# DAC.net
KiCad netlist of a schematic drawn in Altium Designer
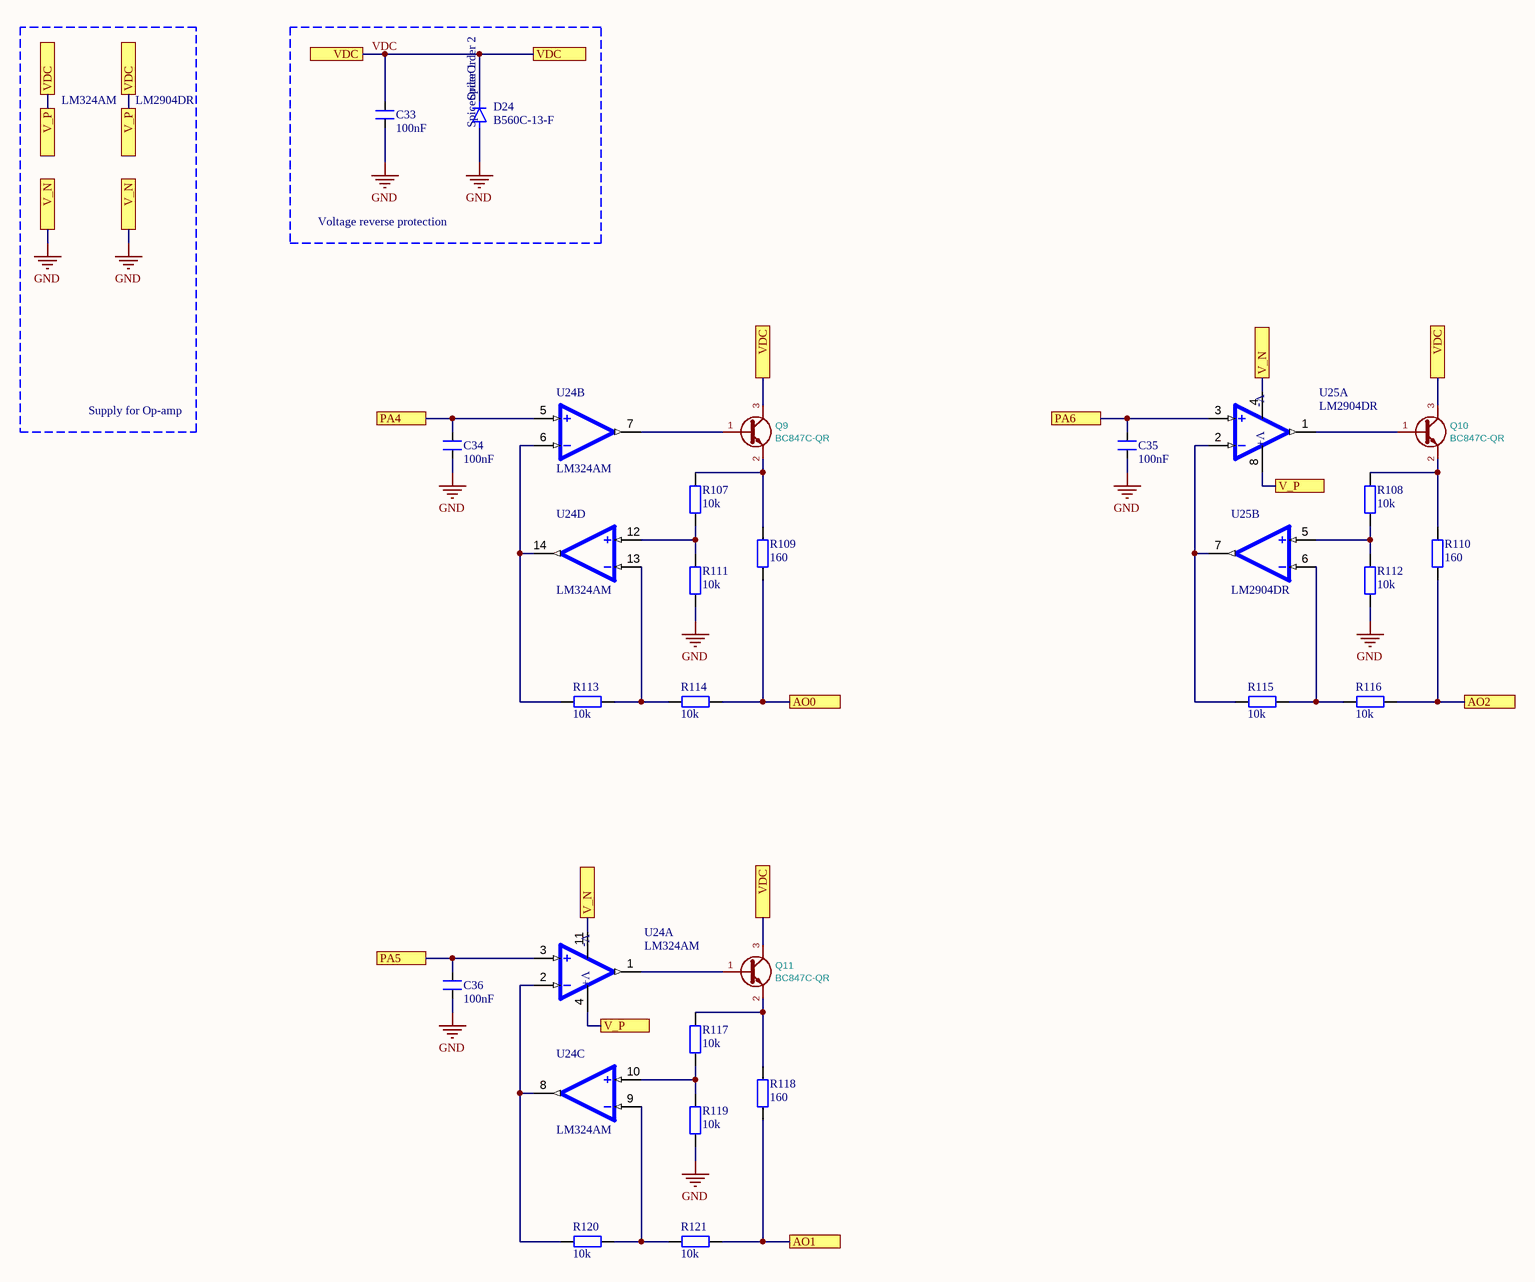
[diagram p0: DAC.SchDoc]

(export (version "E")
  (design (tool "Eeschema 10.0.6"))
  (components
    (comp (ref "C33")
      (value "100nF")
      (footprint "FP-C0603C-CF-IPC_A")
      (description "Capacitor (Semiconductor SIM Model)")
      (fields (field (name "PUBLISHER") "Altium Limited"))
      (libsource (lib "LIBRARY") (part "CN-SEMI-DIP"))
    )
    (comp (ref "C34")
      (value "100nF")
      (footprint "FP-C0603C-CF-IPC_A")
      (description "Capacitor (Semiconductor SIM Model)")
      (fields (field (name "PUBLISHER") "Altium Limited"))
      (libsource (lib "LIBRARY") (part "CN-SEMI-DIP"))
    )
    (comp (ref "C35")
      (value "100nF")
      (footprint "FP-C0603C-CF-IPC_A")
      (description "Capacitor (Semiconductor SIM Model)")
      (fields (field (name "PUBLISHER") "Altium Limited"))
      (libsource (lib "LIBRARY") (part "CN-SEMI-DIP"))
    )
    (comp (ref "C36")
      (value "100nF")
      (footprint "FP-C0603C-CF-IPC_A")
      (description "Capacitor (Semiconductor SIM Model)")
      (fields (field (name "PUBLISHER") "Altium Limited"))
      (libsource (lib "LIBRARY") (part "CN-SEMI-DIP"))
    )
    (comp (ref "D24")
      (value "B560C-13-F")
      (footprint "SMC")
      (description "Diode Schottky 60 V 5A Surface Mount SMC")
      (fields (field (name "MF") "Diodes Inc."))
      (libsource (lib "B560C-13-F") (part "B560C-13-F"))
    )
    (comp (ref "Q9")
      (value "BC847C-QR")
      (footprint "SOT95P240X111-3N")
      (libsource (lib "Transistor_BJT") (part "BC847"))
    )
    (comp (ref "Q10")
      (value "BC847C-QR")
      (footprint "SOT95P240X111-3N")
      (libsource (lib "Transistor_BJT") (part "BC847"))
    )
    (comp (ref "Q11")
      (value "BC847C-QR")
      (footprint "SOT95P240X111-3N")
      (libsource (lib "Transistor_BJT") (part "BC847"))
    )
    (comp (ref "R107")
      (value "10k")
      (footprint "tro smd 0603")
      (description "RES")
      (libsource (lib "AUSB") (part "Tro 0603 1% 10k"))
    )
    (comp (ref "R108")
      (value "10k")
      (footprint "tro smd 0603")
      (description "RES")
      (libsource (lib "AUSB") (part "Tro 0603 1% 10k"))
    )
    (comp (ref "R109")
      (value "160")
      (footprint "tro smd 0603")
      (description "RES")
      (libsource (lib "AUSB") (part "Tro 0603 1% 10k"))
    )
    (comp (ref "R110")
      (value "160")
      (footprint "tro smd 0603")
      (description "RES")
      (libsource (lib "AUSB") (part "Tro 0603 1% 10k"))
    )
    (comp (ref "R111")
      (value "10k")
      (footprint "tro smd 0603")
      (description "RES")
      (libsource (lib "AUSB") (part "Tro 0603 1% 10k"))
    )
    (comp (ref "R112")
      (value "10k")
      (footprint "tro smd 0603")
      (description "RES")
      (libsource (lib "AUSB") (part "Tro 0603 1% 10k"))
    )
    (comp (ref "R113")
      (value "10k")
      (footprint "tro smd 0603")
      (description "RES")
      (libsource (lib "AUSB") (part "Tro 0603 1% 10k"))
    )
    (comp (ref "R114")
      (value "10k")
      (footprint "tro smd 0603")
      (description "RES")
      (libsource (lib "AUSB") (part "Tro 0603 1% 10k"))
    )
    (comp (ref "R115")
      (value "10k")
      (footprint "tro smd 0603")
      (description "RES")
      (libsource (lib "AUSB") (part "Tro 0603 1% 10k"))
    )
    (comp (ref "R116")
      (value "10k")
      (footprint "tro smd 0603")
      (description "RES")
      (libsource (lib "AUSB") (part "Tro 0603 1% 10k"))
    )
    (comp (ref "R117")
      (value "10k")
      (footprint "tro smd 0603")
      (description "RES")
      (libsource (lib "AUSB") (part "Tro 0603 1% 10k"))
    )
    (comp (ref "R118")
      (value "160")
      (footprint "tro smd 0603")
      (description "RES")
      (libsource (lib "AUSB") (part "Tro 0603 1% 10k"))
    )
    (comp (ref "R119")
      (value "10k")
      (footprint "tro smd 0603")
      (description "RES")
      (libsource (lib "AUSB") (part "Tro 0603 1% 10k"))
    )
    (comp (ref "R120")
      (value "10k")
      (footprint "tro smd 0603")
      (description "RES")
      (libsource (lib "AUSB") (part "Tro 0603 1% 10k"))
    )
    (comp (ref "R121")
      (value "10k")
      (footprint "tro smd 0603")
      (description "RES")
      (libsource (lib "AUSB") (part "Tro 0603 1% 10k"))
    )
    (comp (ref "U24")
      (value "LM324AM")
      (footprint "SOIC127P600X175-14N")
      (description "Low power general-purpose quad operational amplifier 14-SOIC 0 to 70")
      (fields (field (name "MF") "Texas Instruments"))
      (libsource (lib "LM324AM_NOPB") (part "LM324AM/NOPB"))
    )
    (comp (ref "U25")
      (value "LM2904DR")
      (footprint "SOIC127P599X175-8N")
      (description "Dual, 26-V, 700-kHz operational amplifier")
      (fields (field (name "MF") "Texas Instruments"))
      (libsource (lib "LM2904DR") (part "LM2904DR"))
    )
  )
  (nets
    (net (code "1") (name "/AO0") (class "Default")
      (node (ref "R109") (pin "1") (pinfunction "1_1") (pintype "passive"))
      (node (ref "R114") (pin "1") (pinfunction "1_1") (pintype "passive"))
    )
    (net (code "2") (name "/AO1") (class "Default")
      (node (ref "R118") (pin "1") (pinfunction "1_1") (pintype "passive"))
      (node (ref "R121") (pin "1") (pinfunction "1_1") (pintype "passive"))
    )
    (net (code "3") (name "/AO2") (class "Default")
      (node (ref "R110") (pin "1") (pinfunction "1_1") (pintype "passive"))
      (node (ref "R116") (pin "1") (pinfunction "1_1") (pintype "passive"))
    )
    (net (code "4") (name "/PA4") (class "Default")
      (node (ref "C34") (pin "1") (pinfunction "1_1") (pintype "passive"))
      (node (ref "U24") (pin "5") (pinfunction "IN2+_5") (pintype "input"))
    )
    (net (code "5") (name "/PA5") (class "Default")
      (node (ref "C36") (pin "1") (pinfunction "1_1") (pintype "passive"))
      (node (ref "U24") (pin "3") (pinfunction "IN1+_3") (pintype "input"))
    )
    (net (code "6") (name "/PA6") (class "Default")
      (node (ref "C35") (pin "1") (pinfunction "1_1") (pintype "passive"))
      (node (ref "U25") (pin "3") (pinfunction "IN1+_3") (pintype "input"))
    )
    (net (code "7") (name "/VDC") (class "Default")
      (node (ref "C33") (pin "1") (pinfunction "1_1") (pintype "passive"))
      (node (ref "D24") (pin "C") (pinfunction "C_C") (pintype "passive"))
      (node (ref "Q10") (pin "3") (pinfunction "C_3") (pintype "passive"))
      (node (ref "Q11") (pin "3") (pinfunction "C_3") (pintype "passive"))
      (node (ref "Q9") (pin "3") (pinfunction "C_3") (pintype "passive"))
      (node (ref "U24") (pin "4") (pinfunction "V+_4") (pintype "power_in"))
      (node (ref "U25") (pin "8") (pinfunction "V+_8") (pintype "power_in"))
    )
    (net (code "8") (name "GND") (class "Default")
      (node (ref "C33") (pin "2") (pinfunction "2_2") (pintype "passive"))
      (node (ref "C34") (pin "2") (pinfunction "2_2") (pintype "passive"))
      (node (ref "C35") (pin "2") (pinfunction "2_2") (pintype "passive"))
      (node (ref "C36") (pin "2") (pinfunction "2_2") (pintype "passive"))
      (node (ref "D24") (pin "A") (pinfunction "A_A") (pintype "passive"))
      (node (ref "R111") (pin "1") (pinfunction "1_1") (pintype "passive"))
      (node (ref "R112") (pin "1") (pinfunction "1_1") (pintype "passive"))
      (node (ref "R119") (pin "1") (pinfunction "1_1") (pintype "passive"))
      (node (ref "U24") (pin "11") (pinfunction "GND_11") (pintype "power_in"))
      (node (ref "U25") (pin "4") (pinfunction "V-_4") (pintype "power_in"))
    )
    (net (code "9") (name "Net-(Q9-B)") (class "Default")
      (node (ref "Q9") (pin "1") (pinfunction "B_1") (pintype "passive"))
      (node (ref "U24") (pin "7") (pinfunction "OUT2_7") (pintype "output"))
    )
    (net (code "10") (name "Net-(Q9-E)") (class "Default")
      (node (ref "Q9") (pin "2") (pinfunction "E_2") (pintype "passive"))
      (node (ref "R107") (pin "2") (pinfunction "2_2") (pintype "passive"))
      (node (ref "R109") (pin "2") (pinfunction "2_2") (pintype "passive"))
    )
    (net (code "11") (name "Net-(Q10-B)") (class "Default")
      (node (ref "Q10") (pin "1") (pinfunction "B_1") (pintype "passive"))
      (node (ref "U25") (pin "1") (pinfunction "OUT1_1") (pintype "output"))
    )
    (net (code "12") (name "Net-(Q10-E)") (class "Default")
      (node (ref "Q10") (pin "2") (pinfunction "E_2") (pintype "passive"))
      (node (ref "R108") (pin "2") (pinfunction "2_2") (pintype "passive"))
      (node (ref "R110") (pin "2") (pinfunction "2_2") (pintype "passive"))
    )
    (net (code "13") (name "Net-(Q11-B)") (class "Default")
      (node (ref "Q11") (pin "1") (pinfunction "B_1") (pintype "passive"))
      (node (ref "U24") (pin "1") (pinfunction "OUT1_1") (pintype "output"))
    )
    (net (code "14") (name "Net-(Q11-E)") (class "Default")
      (node (ref "Q11") (pin "2") (pinfunction "E_2") (pintype "passive"))
      (node (ref "R117") (pin "2") (pinfunction "2_2") (pintype "passive"))
      (node (ref "R118") (pin "2") (pinfunction "2_2") (pintype "passive"))
    )
    (net (code "15") (name "Net-(U24A-IN1-)") (class "Default")
      (node (ref "R120") (pin "2") (pinfunction "2_2") (pintype "passive"))
      (node (ref "U24") (pin "2") (pinfunction "IN1-_2") (pintype "input"))
      (node (ref "U24") (pin "8") (pinfunction "OUT3_8") (pintype "output"))
    )
    (net (code "16") (name "Net-(U24B-IN2-)") (class "Default")
      (node (ref "R113") (pin "2") (pinfunction "2_2") (pintype "passive"))
      (node (ref "U24") (pin "14") (pinfunction "OUT4_14") (pintype "output"))
      (node (ref "U24") (pin "6") (pinfunction "IN2-_6") (pintype "input"))
    )
    (net (code "17") (name "Net-(U24C-IN3+)") (class "Default")
      (node (ref "R117") (pin "1") (pinfunction "1_1") (pintype "passive"))
      (node (ref "R119") (pin "2") (pinfunction "2_2") (pintype "passive"))
      (node (ref "U24") (pin "10") (pinfunction "IN3+_10") (pintype "input"))
    )
    (net (code "18") (name "Net-(U24C-IN3-)") (class "Default")
      (node (ref "R120") (pin "1") (pinfunction "1_1") (pintype "passive"))
      (node (ref "R121") (pin "2") (pinfunction "2_2") (pintype "passive"))
      (node (ref "U24") (pin "9") (pinfunction "IN3-_9") (pintype "input"))
    )
    (net (code "19") (name "Net-(U24D-IN4+)") (class "Default")
      (node (ref "R107") (pin "1") (pinfunction "1_1") (pintype "passive"))
      (node (ref "R111") (pin "2") (pinfunction "2_2") (pintype "passive"))
      (node (ref "U24") (pin "12") (pinfunction "IN4+_12") (pintype "input"))
    )
    (net (code "20") (name "Net-(U24D-IN4-)") (class "Default")
      (node (ref "R113") (pin "1") (pinfunction "1_1") (pintype "passive"))
      (node (ref "R114") (pin "2") (pinfunction "2_2") (pintype "passive"))
      (node (ref "U24") (pin "13") (pinfunction "IN4-_13") (pintype "input"))
    )
    (net (code "21") (name "Net-(U25A-IN1-)") (class "Default")
      (node (ref "R115") (pin "2") (pinfunction "2_2") (pintype "passive"))
      (node (ref "U25") (pin "2") (pinfunction "IN1-_2") (pintype "input"))
      (node (ref "U25") (pin "7") (pinfunction "OUT2_7") (pintype "output"))
    )
    (net (code "22") (name "Net-(U25B-IN2+)") (class "Default")
      (node (ref "R108") (pin "1") (pinfunction "1_1") (pintype "passive"))
      (node (ref "R112") (pin "2") (pinfunction "2_2") (pintype "passive"))
      (node (ref "U25") (pin "5") (pinfunction "IN2+_5") (pintype "input"))
    )
    (net (code "23") (name "Net-(U25B-IN2-)") (class "Default")
      (node (ref "R115") (pin "1") (pinfunction "1_1") (pintype "passive"))
      (node (ref "R116") (pin "2") (pinfunction "2_2") (pintype "passive"))
      (node (ref "U25") (pin "6") (pinfunction "IN2-_6") (pintype "input"))
    )
  )
)
